# EEG_2.net
KiCad netlist of a schematic drawn in EAGLE
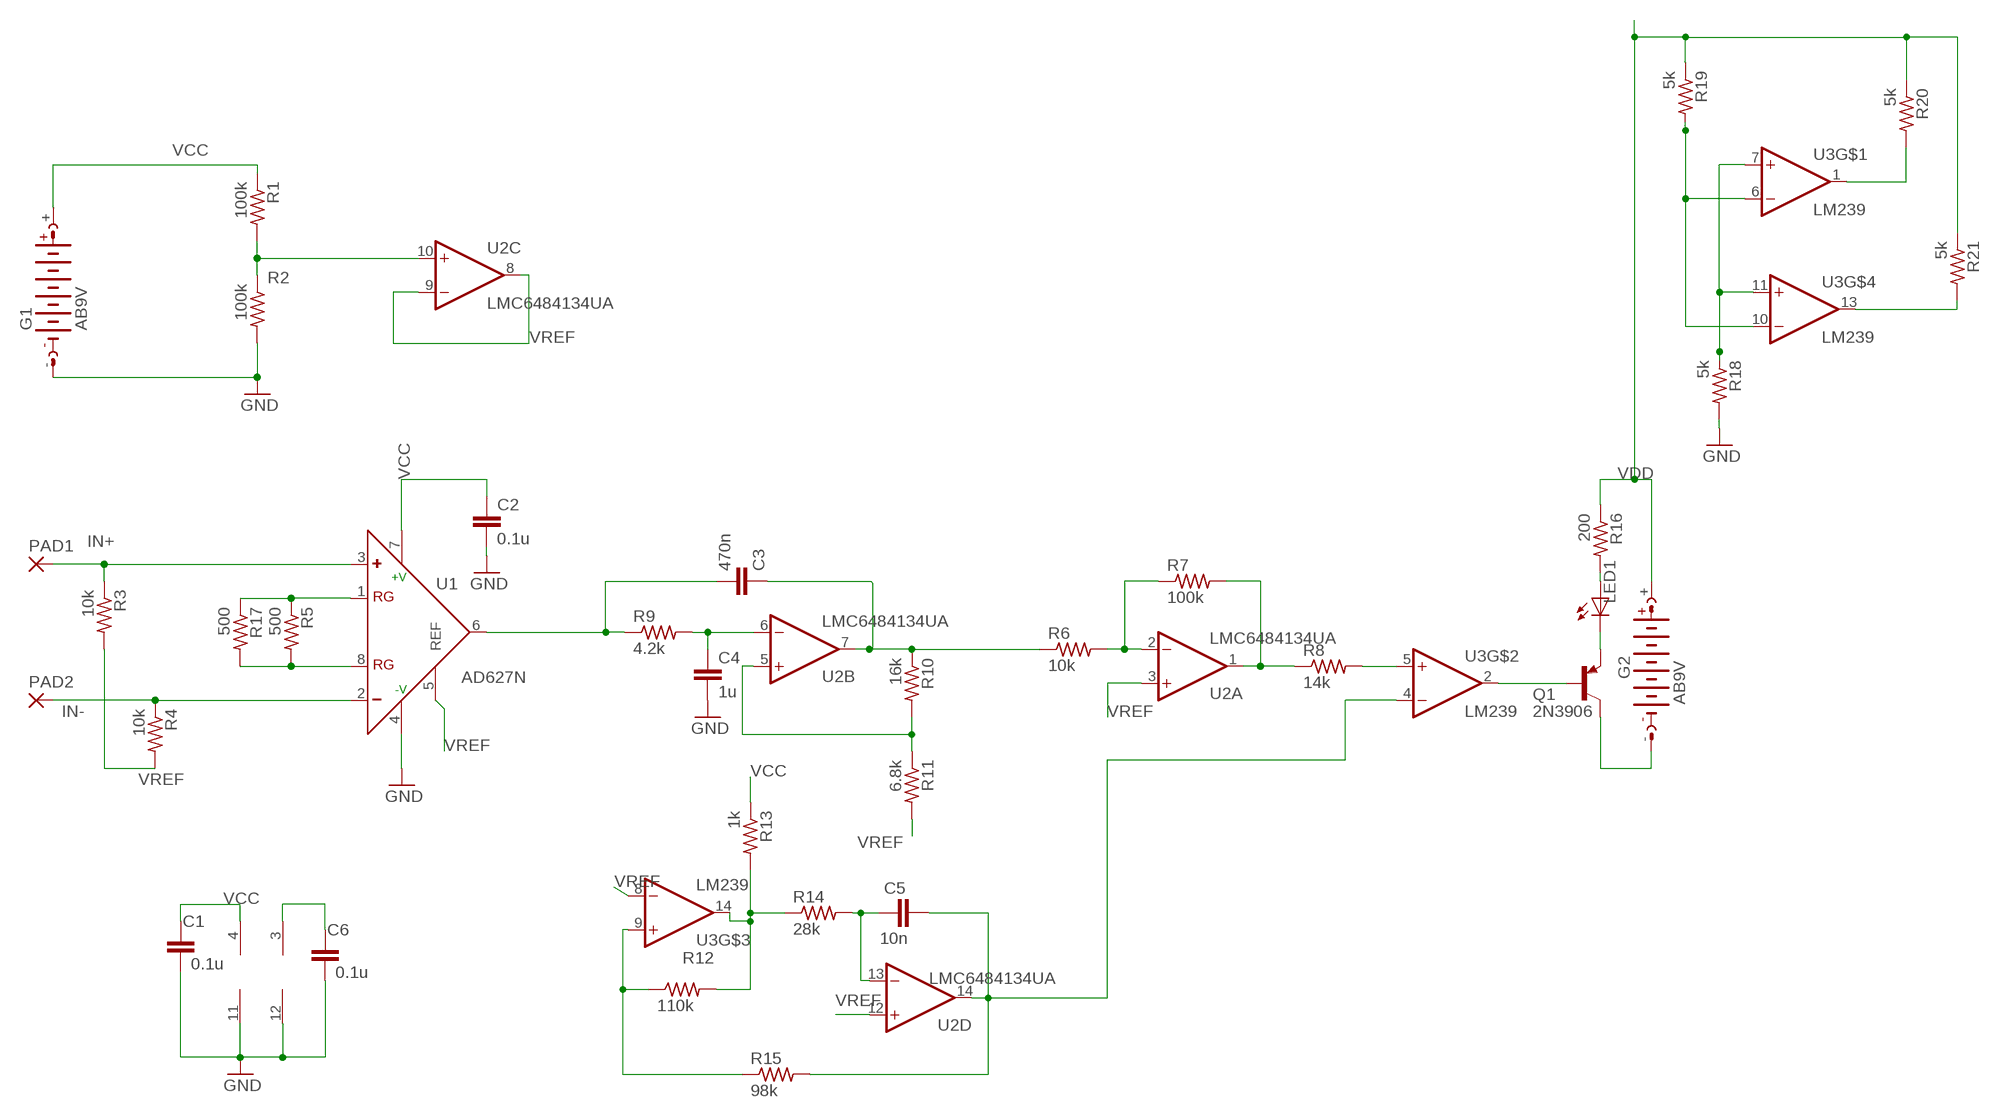
[diagram p0: schematic, sheet 1]

(export (version "E")
  (design (tool "Eeschema 10.0.6"))
  (components
    (comp (ref "C1")
      (value "0.1u")
      (footprint "eagle-import:C5B3")
      (libsource (lib "eagle-import") (part "C5/3"))
    )
    (comp (ref "C2")
      (value "0.1u")
      (footprint "eagle-import:C5B3")
      (libsource (lib "eagle-import") (part "C5/3"))
    )
    (comp (ref "C3")
      (value "470n")
      (footprint "eagle-import:C5B3")
      (libsource (lib "eagle-import") (part "C5/3"))
    )
    (comp (ref "C4")
      (value "1u")
      (footprint "eagle-import:C5B3")
      (libsource (lib "eagle-import") (part "C5/3"))
    )
    (comp (ref "C5")
      (value "10n")
      (footprint "eagle-import:C5B3")
      (libsource (lib "eagle-import") (part "C5/3"))
    )
    (comp (ref "C6")
      (value "0.1u")
      (footprint "eagle-import:C5B3")
      (libsource (lib "eagle-import") (part "C5/3"))
    )
    (comp (ref "G1")
      (value "AB9V")
      (footprint "eagle-import:AB9V")
      (libsource (lib "eagle-import") (part "AB9V"))
    )
    (comp (ref "G2")
      (value "AB9V")
      (footprint "eagle-import:AB9V")
      (libsource (lib "eagle-import") (part "AB9V"))
    )
    (comp (ref "LED1")
      (value "LED5MM")
      (footprint "eagle-import:LED5MM")
      (libsource (lib "eagle-import") (part "LED5MM"))
    )
    (comp (ref "PAD1")
      (value "2,15/1,0")
      (footprint "eagle-import:2,15_1,0")
      (libsource (lib "eagle-import") (part "2,15/1,0"))
    )
    (comp (ref "PAD2")
      (value "2,15/1,0")
      (footprint "eagle-import:2,15_1,0")
      (libsource (lib "eagle-import") (part "2,15/1,0"))
    )
    (comp (ref "Q1")
      (value "2N3906")
      (footprint "eagle-import:TO92")
      (libsource (lib "eagle-import") (part "2N3906"))
    )
    (comp (ref "R1")
      (value "100k")
      (footprint "eagle-import:0207_7")
      (libsource (lib "eagle-import") (part "R-US_0207/7"))
    )
    (comp (ref "R2")
      (value "100k")
      (footprint "eagle-import:0207_7")
      (libsource (lib "eagle-import") (part "R-US_0207/7"))
    )
    (comp (ref "R3")
      (value "10k")
      (footprint "eagle-import:0207_7")
      (libsource (lib "eagle-import") (part "R-US_0207/7"))
    )
    (comp (ref "R4")
      (value "10k")
      (footprint "eagle-import:0207_7")
      (libsource (lib "eagle-import") (part "R-US_0207/7"))
    )
    (comp (ref "R5")
      (value "500")
      (footprint "eagle-import:0207_7")
      (libsource (lib "eagle-import") (part "R-US_0207/7"))
    )
    (comp (ref "R6")
      (value "10k")
      (footprint "eagle-import:0207_7")
      (libsource (lib "eagle-import") (part "R-US_0207/7"))
    )
    (comp (ref "R7")
      (value "100k")
      (footprint "eagle-import:0207_7")
      (libsource (lib "eagle-import") (part "R-US_0207/7"))
    )
    (comp (ref "R8")
      (value "14k")
      (footprint "eagle-import:0207_7")
      (libsource (lib "eagle-import") (part "R-US_0207/7"))
    )
    (comp (ref "R9")
      (value "4.2k")
      (footprint "eagle-import:0207_7")
      (libsource (lib "eagle-import") (part "R-US_0207/7"))
    )
    (comp (ref "R10")
      (value "16k")
      (footprint "eagle-import:0207_7")
      (libsource (lib "eagle-import") (part "R-US_0207/7"))
    )
    (comp (ref "R11")
      (value "6.8k")
      (footprint "eagle-import:0207_7")
      (libsource (lib "eagle-import") (part "R-US_0207/7"))
    )
    (comp (ref "R12")
      (value "110k")
      (footprint "eagle-import:0207_7")
      (libsource (lib "eagle-import") (part "R-US_0207/7"))
    )
    (comp (ref "R13")
      (value "1k")
      (footprint "eagle-import:0207_7")
      (libsource (lib "eagle-import") (part "R-US_0207/7"))
    )
    (comp (ref "R14")
      (value "28k")
      (footprint "eagle-import:0207_7")
      (libsource (lib "eagle-import") (part "R-US_0207/7"))
    )
    (comp (ref "R15")
      (value "98k")
      (footprint "eagle-import:0207_7")
      (libsource (lib "eagle-import") (part "R-US_0207/7"))
    )
    (comp (ref "R16")
      (value "200")
      (footprint "eagle-import:0207_7")
      (libsource (lib "eagle-import") (part "R-US_0207/7"))
    )
    (comp (ref "R17")
      (value "500")
      (footprint "eagle-import:0207_7")
      (libsource (lib "eagle-import") (part "R-US_0207/7"))
    )
    (comp (ref "R18")
      (value "5k")
      (footprint "eagle-import:0207_7")
      (libsource (lib "eagle-import") (part "R-US_0207/7"))
    )
    (comp (ref "R19")
      (value "5k")
      (footprint "eagle-import:0207_7")
      (libsource (lib "eagle-import") (part "R-US_0207/7"))
    )
    (comp (ref "R20")
      (value "5k")
      (footprint "eagle-import:0207_7")
      (libsource (lib "eagle-import") (part "R-US_0207/7"))
    )
    (comp (ref "R21")
      (value "5k")
      (footprint "eagle-import:0207_7")
      (libsource (lib "eagle-import") (part "R-US_0207/7"))
    )
    (comp (ref "U1")
      (value "AD627N")
      (footprint "eagle-import:DIL08")
      (fields (field (name "MF") "ALTERA CORPORATION") (field (name "MPN") "AD627BNZ"))
      (libsource (lib "eagle-import") (part "AD627N"))
    )
    (comp (ref "U2")
      (value "LMC6484134UA")
      (footprint "eagle-import:SO14")
      (libsource (lib "eagle-import") (part "LMC6484UA134"))
    )
    (comp (ref "U3")
      (value "LM239")
      (footprint "eagle-import:SO14")
      (libsource (lib "eagle-import") (part "LM239"))
    )
  )
  (nets
    (net (code "1") (name "/IN+") (class "Default")
      (node (ref "PAD1") (pin "1") (pinfunction "P_1") (pintype "passive"))
      (node (ref "R3") (pin "1") (pinfunction "1_1") (pintype "passive"))
      (node (ref "U1") (pin "3") (pinfunction "+_3") (pintype "input"))
    )
    (net (code "2") (name "/IN-") (class "Default")
      (node (ref "PAD2") (pin "1") (pinfunction "P_1") (pintype "passive"))
      (node (ref "R4") (pin "1") (pinfunction "1_1") (pintype "passive"))
      (node (ref "U1") (pin "2") (pinfunction "-_2") (pintype "input"))
    )
    (net (code "3") (name "/VCC") (class "Default")
      (node (ref "C1") (pin "1") (pinfunction "1_1") (pintype "passive"))
      (node (ref "C2") (pin "1") (pinfunction "1_1") (pintype "passive"))
      (node (ref "G1") (pin "+") (pinfunction "+_+") (pintype "passive"))
      (node (ref "R1") (pin "1") (pinfunction "1_1") (pintype "passive"))
      (node (ref "R13") (pin "1") (pinfunction "1_1") (pintype "passive"))
      (node (ref "U1") (pin "7") (pinfunction "+V_7") (pintype "power_in"))
      (node (ref "U2") (pin "4") (pinfunction "V+_4") (pintype "power_in"))
    )
    (net (code "4") (name "/VDD") (class "Default")
      (node (ref "G2") (pin "+") (pinfunction "+_+") (pintype "passive"))
      (node (ref "R16") (pin "1") (pinfunction "1_1") (pintype "passive"))
      (node (ref "R19") (pin "1") (pinfunction "1_1") (pintype "passive"))
      (node (ref "R20") (pin "1") (pinfunction "1_1") (pintype "passive"))
      (node (ref "R21") (pin "1") (pinfunction "1_1") (pintype "passive"))
    )
    (net (code "5") (name "/VREF") (class "Default")
      (node (ref "R11") (pin "2") (pinfunction "2_2") (pintype "passive"))
      (node (ref "R3") (pin "2") (pinfunction "2_2") (pintype "passive"))
      (node (ref "R4") (pin "2") (pinfunction "2_2") (pintype "passive"))
      (node (ref "U1") (pin "5") (pinfunction "REF_5") (pintype "passive"))
      (node (ref "U2") (pin "12") (pinfunction "+IN_12") (pintype "input"))
      (node (ref "U2") (pin "3") (pinfunction "+IN_3") (pintype "input"))
      (node (ref "U2") (pin "8") (pinfunction "OUT_8") (pintype "output"))
      (node (ref "U2") (pin "9") (pinfunction "-IN_9") (pintype "input"))
      (node (ref "U3") (pin "8") (pinfunction "-IN_8") (pintype "input"))
    )
    (net (code "6") (name "GND") (class "Default")
      (node (ref "C1") (pin "2") (pinfunction "2_2") (pintype "passive"))
      (node (ref "C2") (pin "2") (pinfunction "2_2") (pintype "passive"))
      (node (ref "C4") (pin "2") (pinfunction "2_2") (pintype "passive"))
      (node (ref "C6") (pin "2") (pinfunction "2_2") (pintype "passive"))
      (node (ref "G1") (pin "-") (pinfunction "-_-") (pintype "passive"))
      (node (ref "R18") (pin "2") (pinfunction "2_2") (pintype "passive"))
      (node (ref "R2") (pin "2") (pinfunction "2_2") (pintype "passive"))
      (node (ref "U1") (pin "4") (pinfunction "-V_4") (pintype "power_in"))
      (node (ref "U2") (pin "11") (pinfunction "V-_11") (pintype "power_in"))
      (node (ref "U3") (pin "12") (pinfunction "V-_12") (pintype "power_in"))
    )
    (net (code "7") (name "Net-(LED1-C)") (class "Default")
      (node (ref "LED1") (pin "K") (pinfunction "C_K") (pintype "passive"))
      (node (ref "Q1") (pin "3") (pinfunction "E_3") (pintype "passive"))
    )
    (net (code "8") (name "Net-(LED1-PadA)") (class "Default")
      (node (ref "LED1") (pin "A") (pinfunction "A_A") (pintype "passive"))
      (node (ref "R16") (pin "2") (pinfunction "2_2") (pintype "passive"))
    )
    (net (code "9") (name "Net-(Q1-B)") (class "Default")
      (node (ref "Q1") (pin "2") (pinfunction "B_2") (pintype "passive"))
      (node (ref "U3") (pin "2") (pinfunction "OUT_2") (pintype "output"))
    )
    (net (code "10") (name "Net-(Q1-C)") (class "Default")
      (node (ref "G2") (pin "-") (pinfunction "-_-") (pintype "passive"))
      (node (ref "Q1") (pin "1") (pinfunction "C_1") (pintype "passive"))
    )
    (net (code "11") (name "Net-(R17-Pad1)") (class "Default")
      (node (ref "R17") (pin "1") (pinfunction "1_1") (pintype "passive"))
      (node (ref "R5") (pin "1") (pinfunction "1_1") (pintype "passive"))
      (node (ref "U1") (pin "1") (pinfunction "RG_1") (pintype "passive"))
    )
    (net (code "12") (name "Net-(R17-Pad2)") (class "Default")
      (node (ref "R17") (pin "2") (pinfunction "2_2") (pintype "passive"))
      (node (ref "R5") (pin "2") (pinfunction "2_2") (pintype "passive"))
      (node (ref "U1") (pin "8") (pinfunction "RG_8") (pintype "passive"))
    )
    (net (code "13") (name "Net-(U1-OUT)") (class "Default")
      (node (ref "C3") (pin "1") (pinfunction "1_1") (pintype "passive"))
      (node (ref "R9") (pin "1") (pinfunction "1_1") (pintype "passive"))
      (node (ref "U1") (pin "6") (pinfunction "OUT_6") (pintype "output"))
    )
    (net (code "14") (name "Net-(U2A--IN)") (class "Default")
      (node (ref "R6") (pin "2") (pinfunction "2_2") (pintype "passive"))
      (node (ref "R7") (pin "1") (pinfunction "1_1") (pintype "passive"))
      (node (ref "U2") (pin "2") (pinfunction "-IN_2") (pintype "input"))
    )
    (net (code "15") (name "Net-(U2A-OUT)") (class "Default")
      (node (ref "R7") (pin "2") (pinfunction "2_2") (pintype "passive"))
      (node (ref "R8") (pin "1") (pinfunction "1_1") (pintype "passive"))
      (node (ref "U2") (pin "1") (pinfunction "OUT_1") (pintype "output"))
    )
    (net (code "16") (name "Net-(U2B-+IN)") (class "Default")
      (node (ref "R10") (pin "2") (pinfunction "2_2") (pintype "passive"))
      (node (ref "R11") (pin "1") (pinfunction "1_1") (pintype "passive"))
      (node (ref "U2") (pin "5") (pinfunction "+IN_5") (pintype "input"))
    )
    (net (code "17") (name "Net-(U2B--IN)") (class "Default")
      (node (ref "C4") (pin "1") (pinfunction "1_1") (pintype "passive"))
      (node (ref "R9") (pin "2") (pinfunction "2_2") (pintype "passive"))
      (node (ref "U2") (pin "6") (pinfunction "-IN_6") (pintype "input"))
    )
    (net (code "18") (name "Net-(U2B-OUT)") (class "Default")
      (node (ref "C3") (pin "2") (pinfunction "2_2") (pintype "passive"))
      (node (ref "R10") (pin "1") (pinfunction "1_1") (pintype "passive"))
      (node (ref "R6") (pin "1") (pinfunction "1_1") (pintype "passive"))
      (node (ref "U2") (pin "7") (pinfunction "OUT_7") (pintype "output"))
    )
    (net (code "19") (name "Net-(U2C-+IN)") (class "Default")
      (node (ref "R1") (pin "2") (pinfunction "2_2") (pintype "passive"))
      (node (ref "R2") (pin "1") (pinfunction "1_1") (pintype "passive"))
      (node (ref "U2") (pin "10") (pinfunction "+IN_10") (pintype "input"))
    )
    (net (code "20") (name "Net-(U2D--IN)") (class "Default")
      (node (ref "C5") (pin "2") (pinfunction "2_2") (pintype "passive"))
      (node (ref "R14") (pin "2") (pinfunction "2_2") (pintype "passive"))
      (node (ref "U2") (pin "13") (pinfunction "-IN_13") (pintype "input"))
    )
    (net (code "21") (name "Net-(U2D-OUT)") (class "Default")
      (node (ref "C5") (pin "1") (pinfunction "1_1") (pintype "passive"))
      (node (ref "R15") (pin "2") (pinfunction "2_2") (pintype "passive"))
      (node (ref "U2") (pin "14") (pinfunction "OUT_14") (pintype "output"))
      (node (ref "U3") (pin "4") (pinfunction "-IN_4") (pintype "input"))
    )
    (net (code "22") (name "Net-(U3A-+IN)") (class "Default")
      (node (ref "R18") (pin "1") (pinfunction "1_1") (pintype "passive"))
      (node (ref "U3") (pin "11") (pinfunction "+IN_11") (pintype "input"))
      (node (ref "U3") (pin "7") (pinfunction "+IN_7") (pintype "input"))
    )
    (net (code "23") (name "Net-(U3A--IN)") (class "Default")
      (node (ref "R19") (pin "2") (pinfunction "2_2") (pintype "passive"))
      (node (ref "U3") (pin "10") (pinfunction "-IN_10") (pintype "input"))
      (node (ref "U3") (pin "6") (pinfunction "-IN_6") (pintype "input"))
    )
    (net (code "24") (name "Net-(U3A-OUT)") (class "Default")
      (node (ref "R20") (pin "2") (pinfunction "2_2") (pintype "passive"))
      (node (ref "U3") (pin "1") (pinfunction "OUT_1") (pintype "output"))
    )
    (net (code "25") (name "Net-(U3B-+IN)") (class "Default")
      (node (ref "R8") (pin "2") (pinfunction "2_2") (pintype "passive"))
      (node (ref "U3") (pin "5") (pinfunction "+IN_5") (pintype "input"))
    )
    (net (code "26") (name "Net-(U3C-+IN)") (class "Default")
      (node (ref "R12") (pin "1") (pinfunction "1_1") (pintype "passive"))
      (node (ref "R15") (pin "1") (pinfunction "1_1") (pintype "passive"))
      (node (ref "U3") (pin "9") (pinfunction "+IN_9") (pintype "input"))
    )
    (net (code "27") (name "Net-(U3C-OUT)") (class "Default")
      (node (ref "R12") (pin "2") (pinfunction "2_2") (pintype "passive"))
      (node (ref "R13") (pin "2") (pinfunction "2_2") (pintype "passive"))
      (node (ref "R14") (pin "1") (pinfunction "1_1") (pintype "passive"))
      (node (ref "U3") (pin "14") (pinfunction "OUT_14") (pintype "output"))
    )
    (net (code "28") (name "Net-(U3D-OUT)") (class "Default")
      (node (ref "R21") (pin "2") (pinfunction "2_2") (pintype "passive"))
      (node (ref "U3") (pin "13") (pinfunction "OUT_13") (pintype "output"))
    )
    (net (code "29") (name "Net-(U3E-V+)") (class "Default")
      (node (ref "C6") (pin "1") (pinfunction "1_1") (pintype "passive"))
      (node (ref "U3") (pin "3") (pinfunction "V+_3") (pintype "power_in"))
    )
  )
)
